# ft231x-micro.net
KiCad netlist of a schematic drawn in EAGLE
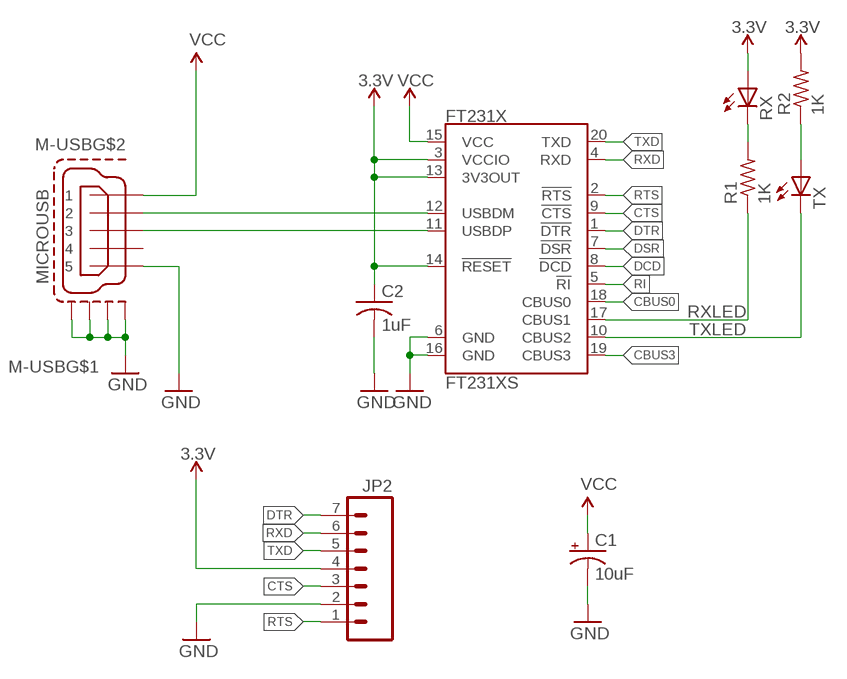
[diagram p0: schematic, sheet 1]

(export (version "E")
  (design (tool "Eeschema 10.0.6"))
  (components
    (comp (ref "C1")
      (value "10uF")
      (footprint "eagle-import:EIA3216")
      (libsource (lib "eagle-import") (part "CAP_POL1206"))
    )
    (comp (ref "C2")
      (value "1uF")
      (footprint "eagle-import:C0805")
      (libsource (lib "eagle-import") (part "C-USC0805"))
    )
    (comp (ref "FT231X")
      (value "FT231XS")
      (footprint "eagle-import:SSOP20_L")
      (libsource (lib "eagle-import") (part "FT231XS"))
    )
    (comp (ref "JP2")
      (value "M07")
      (footprint "eagle-import:1X07")
      (libsource (lib "eagle-import") (part "M07"))
    )
    (comp (ref "M-USB")
      (value "MICROUSB")
      (footprint "eagle-import:ZX62R-B-5P")
      (libsource (lib "eagle-import") (part "MICRO-USB-SHIELD-ZX62R-B-5P"))
    )
    (comp (ref "R1")
      (value "1K")
      (footprint "eagle-import:R0603")
      (libsource (lib "eagle-import") (part "R-US_R0603"))
    )
    (comp (ref "R2")
      (value "1K")
      (footprint "eagle-import:R0603")
      (libsource (lib "eagle-import") (part "R-US_R0603"))
    )
    (comp (ref "RX")
      (value "LEDCHIP-LED0805")
      (footprint "eagle-import:CHIP-LED0805")
      (libsource (lib "eagle-import") (part "LEDCHIP-LED0805"))
    )
    (comp (ref "TX")
      (value "LEDCHIP-LED0805")
      (footprint "eagle-import:CHIP-LED0805")
      (libsource (lib "eagle-import") (part "LEDCHIP-LED0805"))
    )
  )
  (nets
    (net (code "1") (name "/RXLED") (class "Default")
      (node (ref "FT231X") (pin "17") (pinfunction "CBUS1_17") (pintype "bidirectional"))
      (node (ref "R1") (pin "1") (pinfunction "1_1") (pintype "passive"))
    )
    (net (code "2") (name "/TXLED") (class "Default")
      (node (ref "FT231X") (pin "10") (pinfunction "CBUS2_10") (pintype "bidirectional"))
      (node (ref "TX") (pin "C") (pinfunction "C_C") (pintype "passive"))
    )
    (net (code "3") (name "3.3V") (class "Default")
      (node (ref "C2") (pin "1") (pinfunction "1_1") (pintype "passive"))
      (node (ref "FT231X") (pin "13") (pinfunction "3V3OUT_13") (pintype "bidirectional"))
      (node (ref "FT231X") (pin "14") (pinfunction "~{RESET}_14") (pintype "bidirectional"))
      (node (ref "FT231X") (pin "3") (pinfunction "VCCIO_3") (pintype "bidirectional"))
      (node (ref "JP2") (pin "4") (pinfunction "4_4") (pintype "passive"))
      (node (ref "R2") (pin "2") (pinfunction "2_2") (pintype "passive"))
      (node (ref "RX") (pin "A") (pinfunction "A_A") (pintype "passive"))
    )
    (net (code "4") (name "CBUS0") (class "Default")
      (node (ref "FT231X") (pin "18") (pinfunction "CBUS0_18") (pintype "bidirectional"))
    )
    (net (code "5") (name "CBUS3") (class "Default")
      (node (ref "FT231X") (pin "19") (pinfunction "CBUS3_19") (pintype "bidirectional"))
    )
    (net (code "6") (name "CTS") (class "Default")
      (node (ref "FT231X") (pin "9") (pinfunction "~{CTS}_9") (pintype "bidirectional"))
      (node (ref "JP2") (pin "3") (pinfunction "3_3") (pintype "passive"))
    )
    (net (code "7") (name "DCD") (class "Default")
      (node (ref "FT231X") (pin "8") (pinfunction "~{DCD}_8") (pintype "bidirectional"))
    )
    (net (code "8") (name "DSR") (class "Default")
      (node (ref "FT231X") (pin "7") (pinfunction "~{DSR}_7") (pintype "bidirectional"))
    )
    (net (code "9") (name "DTR") (class "Default")
      (node (ref "FT231X") (pin "1") (pinfunction "~{DTR}_1") (pintype "bidirectional"))
      (node (ref "JP2") (pin "7") (pinfunction "7_7") (pintype "passive"))
    )
    (net (code "10") (name "GND") (class "Default")
      (node (ref "C1") (pin "C") (pinfunction "-_C") (pintype "passive"))
      (node (ref "C2") (pin "2") (pinfunction "2_2") (pintype "passive"))
      (node (ref "FT231X") (pin "16") (pinfunction "GND_16") (pintype "bidirectional"))
      (node (ref "FT231X") (pin "6") (pinfunction "GND_6") (pintype "bidirectional"))
      (node (ref "JP2") (pin "2") (pinfunction "2_2") (pintype "passive"))
      (node (ref "M-USB") (pin "5") (pinfunction "5_5") (pintype "input"))
      (node (ref "M-USB") (pin "M1") (pinfunction "S1_M1") (pintype "passive"))
      (node (ref "M-USB") (pin "M2") (pinfunction "S2_M2") (pintype "passive"))
      (node (ref "M-USB") (pin "M3") (pinfunction "S3_M3") (pintype "passive"))
      (node (ref "M-USB") (pin "M4") (pinfunction "S4_M4") (pintype "passive"))
    )
    (net (code "11") (name "Net-(FT231X-USBDM)") (class "Default")
      (node (ref "FT231X") (pin "12") (pinfunction "USBDM_12") (pintype "bidirectional"))
      (node (ref "M-USB") (pin "2") (pinfunction "2_2") (pintype "input"))
    )
    (net (code "12") (name "Net-(FT231X-USBDP)") (class "Default")
      (node (ref "FT231X") (pin "11") (pinfunction "USBDP_11") (pintype "bidirectional"))
      (node (ref "M-USB") (pin "3") (pinfunction "3_3") (pintype "input"))
    )
    (net (code "13") (name "Net-(R1-Pad2)") (class "Default")
      (node (ref "R1") (pin "2") (pinfunction "2_2") (pintype "passive"))
      (node (ref "RX") (pin "C") (pinfunction "C_C") (pintype "passive"))
    )
    (net (code "14") (name "Net-(R2-Pad1)") (class "Default")
      (node (ref "R2") (pin "1") (pinfunction "1_1") (pintype "passive"))
      (node (ref "TX") (pin "A") (pinfunction "A_A") (pintype "passive"))
    )
    (net (code "15") (name "RI") (class "Default")
      (node (ref "FT231X") (pin "5") (pinfunction "~{RI}_5") (pintype "bidirectional"))
    )
    (net (code "16") (name "RTS") (class "Default")
      (node (ref "FT231X") (pin "2") (pinfunction "~{RTS}_2") (pintype "bidirectional"))
      (node (ref "JP2") (pin "1") (pinfunction "1_1") (pintype "passive"))
    )
    (net (code "17") (name "RXD") (class "Default")
      (node (ref "FT231X") (pin "4") (pinfunction "RXD_4") (pintype "bidirectional"))
      (node (ref "JP2") (pin "6") (pinfunction "6_6") (pintype "passive"))
    )
    (net (code "18") (name "TXD") (class "Default")
      (node (ref "FT231X") (pin "20") (pinfunction "TXD_20") (pintype "bidirectional"))
      (node (ref "JP2") (pin "5") (pinfunction "5_5") (pintype "passive"))
    )
    (net (code "19") (name "VCC") (class "Default")
      (node (ref "C1") (pin "A") (pinfunction "+_A") (pintype "passive"))
      (node (ref "FT231X") (pin "15") (pinfunction "VCC_15") (pintype "bidirectional"))
      (node (ref "M-USB") (pin "1") (pinfunction "1_1") (pintype "input"))
    )
    (net (code "20") (name "unconnected-(M-USB-Pad4)") (class "Default")
      (node (ref "M-USB") (pin "4") (pinfunction "4_4") (pintype "input"))
    )
  )
)
